# Power.net
KiCad netlist of a schematic drawn in Altium Designer
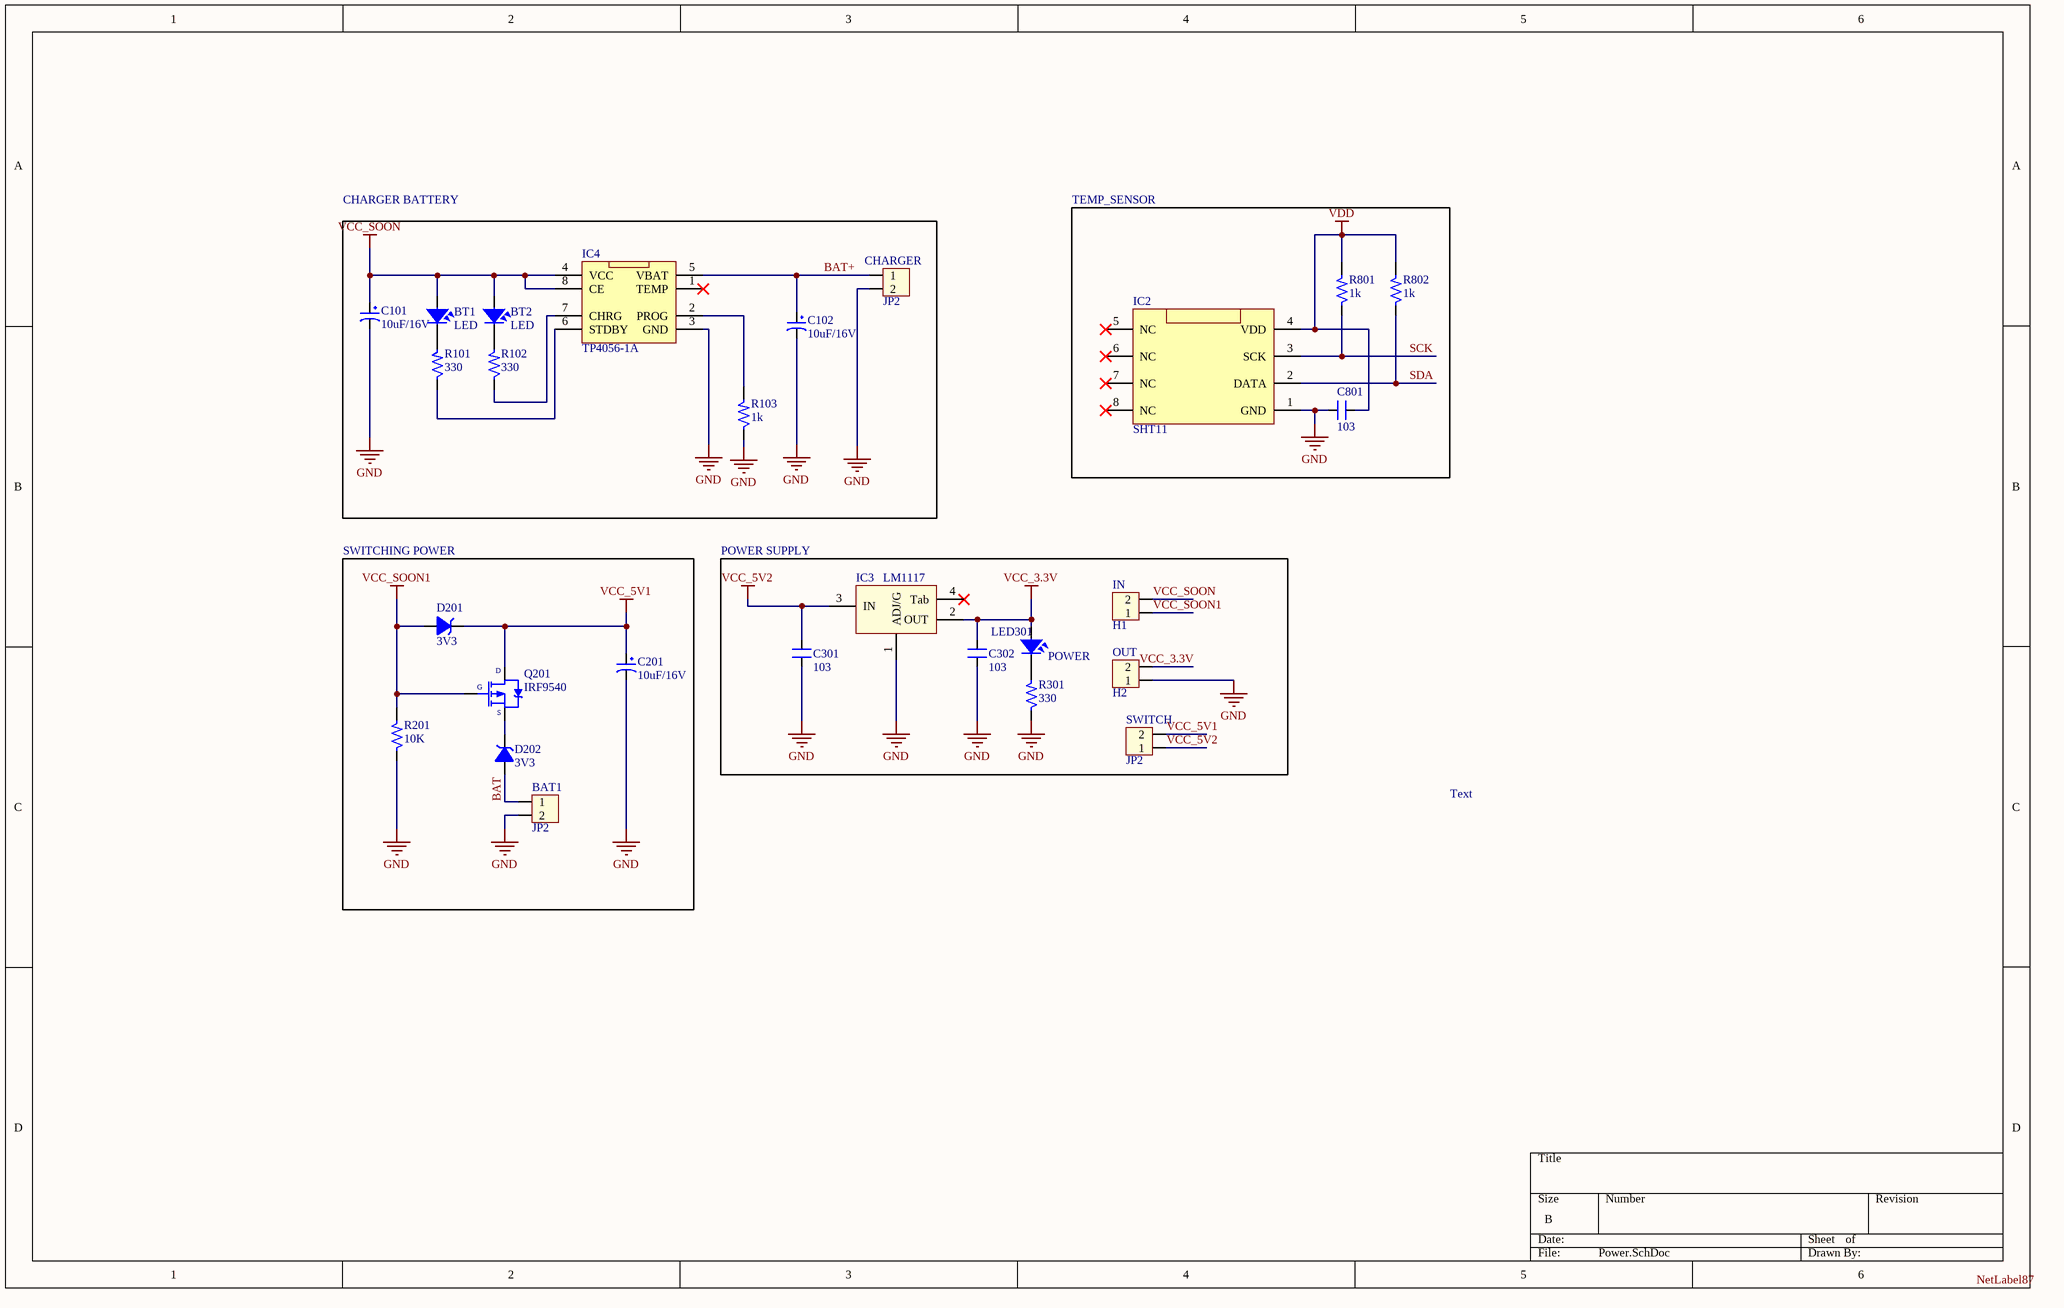
[diagram p0: Power.SchDoc]

(export (version "E")
  (design (tool "Eeschema 10.0.6"))
  (components
    (comp (ref "BAT1")
      (value "JP2")
      (footprint "CON2")
      (description "Connector 2")
      (libsource (lib "syhaunguyen") (part "Con2"))
    )
    (comp (ref "BT1")
      (value "LED")
      (footprint "LED0805-Blue")
      (description "LED Single colour Green and Red")
      (libsource (lib "syhaunguyen") (part "LED"))
    )
    (comp (ref "BT2")
      (value "LED")
      (footprint "LED0805-Blue")
      (description "LED Single colour Green and Red")
      (libsource (lib "syhaunguyen") (part "LED"))
    )
    (comp (ref "C101")
      (value "10uF/16V")
      (footprint "CAP-B-22UF/16V")
      (description "Cap 100uF/35V - 470uF/16V")
      (libsource (lib "syhaunguyen") (part "CP3"))
    )
    (comp (ref "C102")
      (value "10uF/16V")
      (footprint "CAP-B-22UF/16V")
      (description "Cap 100uF/35V - 470uF/16V")
      (libsource (lib "syhaunguyen") (part "CP3"))
    )
    (comp (ref "C201")
      (value "10uF/16V")
      (footprint "CAP-B-22UF/16V")
      (description "Cap 100uF/35V - 470uF/16V")
      (libsource (lib "syhaunguyen") (part "CP3"))
    )
    (comp (ref "C301")
      (value "103")
      (footprint "SM-0805")
      (description "Cap SMD")
      (libsource (lib "syhaunguyen") (part "CM"))
    )
    (comp (ref "C302")
      (value "103")
      (footprint "SM-0805")
      (description "Cap SMD")
      (libsource (lib "syhaunguyen") (part "CM"))
    )
    (comp (ref "C801")
      (value "103")
      (footprint "SM-0805")
      (description "Cap SMD")
      (libsource (lib "syhaunguyen") (part "CM"))
    )
    (comp (ref "CHARGER")
      (value "JP2")
      (footprint "CON2")
      (description "Connector 2")
      (libsource (lib "syhaunguyen") (part "Con2"))
    )
    (comp (ref "D201")
      (value "3V3")
      (footprint "Diode1206")
      (description "Diode Zenner")
      (libsource (lib "syhaunguyen") (part "DZ"))
    )
    (comp (ref "D202")
      (value "3V3")
      (footprint "Diode1206")
      (description "Diode Zenner")
      (libsource (lib "syhaunguyen") (part "DZ"))
    )
    (comp (ref "IC2") (value "SHT11") (libsource (lib "syhaunguyen") (part "SHT11")))
    (comp (ref "IC3")
      (value "LM1117")
      (footprint "SOT223-4N")
      (description "3v3")
      (libsource (lib "syhaunguyen") (part "LM1117"))
    )
    (comp (ref "IC4")
      (value "TP4056-1A")
      (footprint "TP4056-1A")
      (libsource (lib "Nupakachi") (part "TP4056-1A"))
    )
    (comp (ref "IN")
      (value "H1")
      (footprint "CON2")
      (description "Header 2 (Green)")
      (libsource (lib "syhaunguyen") (part "Hed2"))
    )
    (comp (ref "LED301")
      (value "POWER")
      (footprint "LED0805-Blue")
      (description "LED Single colour Green and Red")
      (libsource (lib "syhaunguyen") (part "LED"))
    )
    (comp (ref "OUT")
      (value "H2")
      (footprint "CON2")
      (description "Header 2 (Green)")
      (libsource (lib "syhaunguyen") (part "Hed2"))
    )
    (comp (ref "Q201")
      (value "IRF9540")
      (footprint "SOT23A")
      (description "HEXFET P-Channel Power MOSFET")
      (fields (field (name "PUBLISHER") "Altium Limited"))
      (libsource (lib "syhaunguyen") (part "IRF9540"))
    )
    (comp (ref "R101")
      (value "330")
      (footprint "SM-0805")
      (description "Resistor 1/4W")
      (libsource (lib "syhaunguyen") (part "R"))
    )
    (comp (ref "R102")
      (value "330")
      (footprint "SM-0805")
      (description "Resistor 1/4W")
      (libsource (lib "syhaunguyen") (part "R"))
    )
    (comp (ref "R103")
      (value "1k")
      (footprint "SM-0805")
      (description "Resistor 1/4W")
      (libsource (lib "syhaunguyen") (part "R"))
    )
    (comp (ref "R201")
      (value "10K")
      (footprint "SM-0805")
      (description "Resistor 1/4W")
      (libsource (lib "syhaunguyen") (part "R"))
    )
    (comp (ref "R301")
      (value "330")
      (footprint "SM-0805")
      (description "Resistor 1/4W")
      (libsource (lib "syhaunguyen") (part "R"))
    )
    (comp (ref "R801")
      (value "1k")
      (footprint "SM-1206")
      (description "Resistor 1/4W")
      (libsource (lib "syhaunguyen") (part "R"))
    )
    (comp (ref "R802")
      (value "1k")
      (footprint "SM-1206")
      (description "Resistor 1/4W")
      (libsource (lib "syhaunguyen") (part "R"))
    )
    (comp (ref "SWITCH")
      (value "JP2")
      (footprint "CON2")
      (description "Connector 2")
      (libsource (lib "") (part "Con2_1"))
    )
  )
  (nets
    (net (code "1") (name "/BAT") (class "Default")
      (node (ref "BAT1") (pin "1") (pinfunction "1_1") (pintype "passive"))
      (node (ref "D202") (pin "1") (pinfunction "A_1") (pintype "passive"))
    )
    (net (code "2") (name "/BAT+") (class "Default")
      (node (ref "C102") (pin "1") (pinfunction "1_1") (pintype "passive"))
      (node (ref "CHARGER") (pin "1") (pinfunction "1_1") (pintype "passive"))
      (node (ref "IC4") (pin "5") (pinfunction "VBAT_5") (pintype "power_in"))
    )
    (net (code "4") (name "/SCK") (class "Default")
      (node (ref "IC2") (pin "3") (pinfunction "SCK_3") (pintype "passive"))
      (node (ref "R801") (pin "1") (pinfunction "1_1") (pintype "passive"))
    )
    (net (code "5") (name "/SDA") (class "Default")
      (node (ref "IC2") (pin "2") (pinfunction "DATA_2") (pintype "passive"))
      (node (ref "R802") (pin "1") (pinfunction "1_1") (pintype "passive"))
    )
    (net (code "6") (name "GND") (class "Default")
      (node (ref "BAT1") (pin "2") (pinfunction "2_2") (pintype "passive"))
      (node (ref "C101") (pin "2") (pinfunction "2_2") (pintype "passive"))
      (node (ref "C102") (pin "2") (pinfunction "2_2") (pintype "passive"))
      (node (ref "C201") (pin "2") (pinfunction "2_2") (pintype "passive"))
      (node (ref "C301") (pin "1") (pinfunction "1_1") (pintype "passive"))
      (node (ref "C302") (pin "1") (pinfunction "1_1") (pintype "passive"))
      (node (ref "C801") (pin "2") (pinfunction "2_2") (pintype "passive"))
      (node (ref "CHARGER") (pin "2") (pinfunction "2_2") (pintype "passive"))
      (node (ref "IC2") (pin "1") (pinfunction "GND_1") (pintype "power_in"))
      (node (ref "IC3") (pin "1") (pinfunction "ADJ/G_1") (pintype "passive"))
      (node (ref "IC4") (pin "3") (pinfunction "GND_3") (pintype "power_in"))
      (node (ref "OUT") (pin "1") (pinfunction "1_1") (pintype "passive"))
      (node (ref "R103") (pin "1") (pinfunction "1_1") (pintype "passive"))
      (node (ref "R201") (pin "1") (pinfunction "1_1") (pintype "passive"))
      (node (ref "R301") (pin "1") (pinfunction "1_1") (pintype "passive"))
    )
    (net (code "7") (name "Net-(BT1-Pad2)") (class "Default")
      (node (ref "BT1") (pin "2") (pinfunction "2_2") (pintype "passive"))
      (node (ref "R101") (pin "2") (pinfunction "2_2") (pintype "passive"))
    )
    (net (code "8") (name "Net-(BT2-Pad2)") (class "Default")
      (node (ref "BT2") (pin "2") (pinfunction "2_2") (pintype "passive"))
      (node (ref "R102") (pin "2") (pinfunction "2_2") (pintype "passive"))
    )
    (net (code "9") (name "Net-(D202-K)") (class "Default")
      (node (ref "D202") (pin "2") (pinfunction "K_2") (pintype "passive"))
      (node (ref "Q201") (pin "3") (pinfunction "S_3") (pintype "passive"))
    )
    (net (code "10") (name "Net-(IC4-CHRG)") (class "Default")
      (node (ref "IC4") (pin "7") (pinfunction "CHRG_7") (pintype "passive"))
      (node (ref "R102") (pin "1") (pinfunction "1_1") (pintype "passive"))
    )
    (net (code "11") (name "Net-(IC4-PROG)") (class "Default")
      (node (ref "IC4") (pin "2") (pinfunction "PROG_2") (pintype "passive"))
      (node (ref "R103") (pin "2") (pinfunction "2_2") (pintype "passive"))
    )
    (net (code "12") (name "Net-(IC4-STDBY)") (class "Default")
      (node (ref "IC4") (pin "6") (pinfunction "STDBY_6") (pintype "passive"))
      (node (ref "R101") (pin "1") (pinfunction "1_1") (pintype "passive"))
    )
    (net (code "13") (name "Net-(LED301-Pad2)") (class "Default")
      (node (ref "LED301") (pin "2") (pinfunction "2_2") (pintype "passive"))
      (node (ref "R301") (pin "2") (pinfunction "2_2") (pintype "passive"))
    )
    (net (code "14") (name "VCC_3.3V") (class "Default")
      (node (ref "C302") (pin "2") (pinfunction "2_2") (pintype "passive"))
      (node (ref "IC3") (pin "2") (pinfunction "OUT_2") (pintype "passive"))
      (node (ref "LED301") (pin "1") (pinfunction "1_1") (pintype "passive"))
    )
    (net (code "15") (name "VCC_5V1") (class "Default")
      (node (ref "C201") (pin "1") (pinfunction "1_1") (pintype "passive"))
      (node (ref "D201") (pin "2") (pinfunction "K_2") (pintype "passive"))
      (node (ref "Q201") (pin "2") (pinfunction "D_2") (pintype "passive"))
      (node (ref "SWITCH") (pin "2") (pinfunction "2_2") (pintype "passive"))
    )
    (net (code "16") (name "VCC_5V2") (class "Default")
      (node (ref "C301") (pin "2") (pinfunction "2_2") (pintype "passive"))
      (node (ref "IC3") (pin "3") (pinfunction "IN_3") (pintype "passive"))
      (node (ref "SWITCH") (pin "1") (pinfunction "1_1") (pintype "passive"))
    )
    (net (code "17") (name "VCC_SOON") (class "Default")
      (node (ref "BT1") (pin "1") (pinfunction "1_1") (pintype "passive"))
      (node (ref "BT2") (pin "1") (pinfunction "1_1") (pintype "passive"))
      (node (ref "C101") (pin "1") (pinfunction "1_1") (pintype "passive"))
      (node (ref "IC4") (pin "4") (pinfunction "VCC_4") (pintype "power_in"))
      (node (ref "IC4") (pin "8") (pinfunction "CE_8") (pintype "passive"))
      (node (ref "IN") (pin "2") (pinfunction "2_2") (pintype "passive"))
    )
    (net (code "18") (name "VCC_SOON1") (class "Default")
      (node (ref "D201") (pin "1") (pinfunction "A_1") (pintype "passive"))
      (node (ref "IN") (pin "1") (pinfunction "1_1") (pintype "passive"))
      (node (ref "Q201") (pin "1") (pinfunction "G_1") (pintype "passive"))
      (node (ref "R201") (pin "2") (pinfunction "2_2") (pintype "passive"))
    )
    (net (code "19") (name "VDD") (class "Default")
      (node (ref "C801") (pin "1") (pinfunction "1_1") (pintype "passive"))
      (node (ref "IC2") (pin "4") (pinfunction "VDD_4") (pintype "power_in"))
      (node (ref "R801") (pin "2") (pinfunction "2_2") (pintype "passive"))
      (node (ref "R802") (pin "2") (pinfunction "2_2") (pintype "passive"))
    )
    (net (code "20") (name "unconnected-(IC2-NC-Pad5)") (class "Default")
      (node (ref "IC2") (pin "5") (pinfunction "NC_5") (pintype "passive+no_connect"))
    )
    (net (code "21") (name "unconnected-(IC2-NC-Pad6)") (class "Default")
      (node (ref "IC2") (pin "6") (pinfunction "NC_6") (pintype "passive+no_connect"))
    )
    (net (code "22") (name "unconnected-(IC2-NC-Pad7)") (class "Default")
      (node (ref "IC2") (pin "7") (pinfunction "NC_7") (pintype "passive+no_connect"))
    )
    (net (code "23") (name "unconnected-(IC2-NC-Pad8)") (class "Default")
      (node (ref "IC2") (pin "8") (pinfunction "NC_8") (pintype "passive+no_connect"))
    )
    (net (code "24") (name "unconnected-(IC3-Tab-Pad4)") (class "Default")
      (node (ref "IC3") (pin "4") (pinfunction "Tab_4") (pintype "passive+no_connect"))
    )
    (net (code "25") (name "unconnected-(IC4-TEMP-Pad1)") (class "Default")
      (node (ref "IC4") (pin "1") (pinfunction "TEMP_1") (pintype "passive+no_connect"))
    )
    (net (code "26") (name "unconnected-(OUT-Pad2)") (class "Default")
      (node (ref "OUT") (pin "2") (pinfunction "2_2") (pintype "passive"))
    )
  )
)
